# chematic_badar_ahmad_anggoro.net
KiCad netlist of a schematic drawn in EAGLE
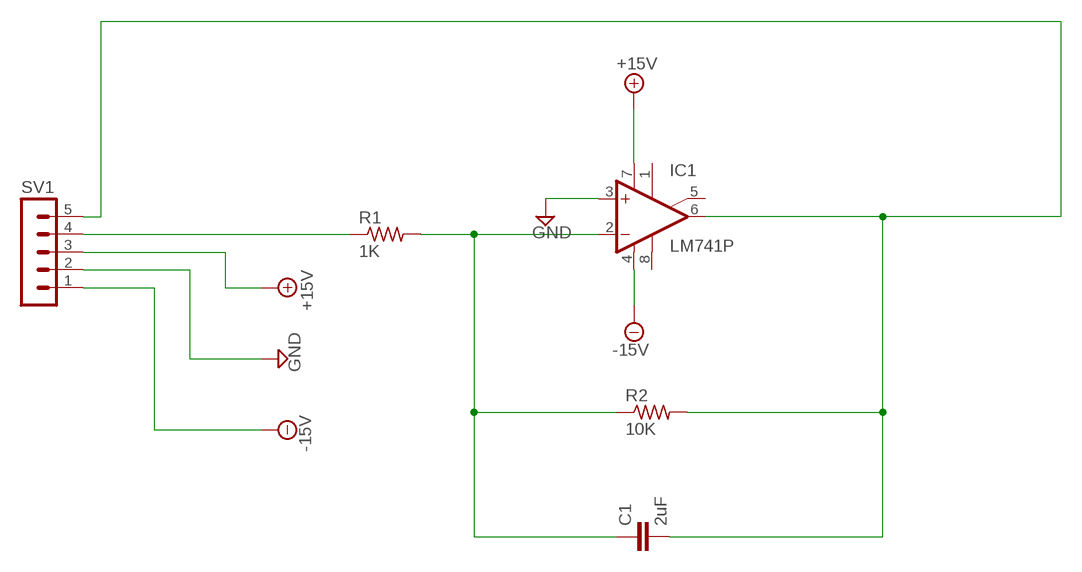
[diagram p0: schematic, sheet 1]

(export (version "E")
  (design (tool "Eeschema 10.0.6"))
  (components
    (comp (ref "C1")
      (value "2uF")
      (footprint "eagle-import:C025-024X044")
      (libsource (lib "eagle-import") (part "C-EU025-024X044"))
    )
    (comp (ref "IC1")
      (value "LM741P")
      (footprint "eagle-import:DIL08")
      (libsource (lib "eagle-import") (part "741PLM"))
    )
    (comp (ref "R1")
      (value "1K")
      (footprint "eagle-import:0204_5")
      (libsource (lib "eagle-import") (part "R-US_0204/5"))
    )
    (comp (ref "R2")
      (value "10K")
      (footprint "eagle-import:0204_5")
      (libsource (lib "eagle-import") (part "R-US_0204/5"))
    )
    (comp (ref "SV1")
      (value "MA05-1")
      (footprint "eagle-import:MA05-1")
      (libsource (lib "eagle-import") (part "MA05-1"))
    )
  )
  (nets
    (net (code "1") (name "+15V") (class "Default")
      (node (ref "IC1") (pin "7") (pinfunction "V+_7") (pintype "power_in"))
      (node (ref "SV1") (pin "3") (pinfunction "3_3") (pintype "passive"))
    )
    (net (code "2") (name "-15V") (class "Default")
      (node (ref "IC1") (pin "4") (pinfunction "V-_4") (pintype "power_in"))
      (node (ref "SV1") (pin "1") (pinfunction "1_1") (pintype "passive"))
    )
    (net (code "3") (name "GND") (class "Default")
      (node (ref "IC1") (pin "3") (pinfunction "+IN_3") (pintype "input"))
      (node (ref "SV1") (pin "2") (pinfunction "2_2") (pintype "passive"))
    )
    (net (code "4") (name "Net-(IC1--IN)") (class "Default")
      (node (ref "C1") (pin "1") (pinfunction "1_1") (pintype "passive"))
      (node (ref "IC1") (pin "2") (pinfunction "-IN_2") (pintype "input"))
      (node (ref "R1") (pin "2") (pinfunction "2_2") (pintype "passive"))
      (node (ref "R2") (pin "1") (pinfunction "1_1") (pintype "passive"))
    )
    (net (code "5") (name "Net-(IC1-OUT)") (class "Default")
      (node (ref "C1") (pin "2") (pinfunction "2_2") (pintype "passive"))
      (node (ref "IC1") (pin "6") (pinfunction "OUT_6") (pintype "output"))
      (node (ref "R2") (pin "2") (pinfunction "2_2") (pintype "passive"))
      (node (ref "SV1") (pin "5") (pinfunction "5_5") (pintype "passive"))
    )
    (net (code "6") (name "Net-(R1-Pad1)") (class "Default")
      (node (ref "R1") (pin "1") (pinfunction "1_1") (pintype "passive"))
      (node (ref "SV1") (pin "4") (pinfunction "4_4") (pintype "passive"))
    )
    (net (code "7") (name "unconnected-(IC1-ON1-Pad1)") (class "Default")
      (node (ref "IC1") (pin "1") (pinfunction "ON1_1") (pintype "passive"))
    )
    (net (code "8") (name "unconnected-(IC1-ON2-Pad5)") (class "Default")
      (node (ref "IC1") (pin "5") (pinfunction "ON2_5") (pintype "passive"))
    )
    (net (code "9") (name "unconnected-(IC1-OPT-Pad8)") (class "Default")
      (node (ref "IC1") (pin "8") (pinfunction "OPT_8") (pintype "passive"))
    )
  )
)
